# optocouplers2.net
KiCad netlist of a schematic drawn in Altium Designer
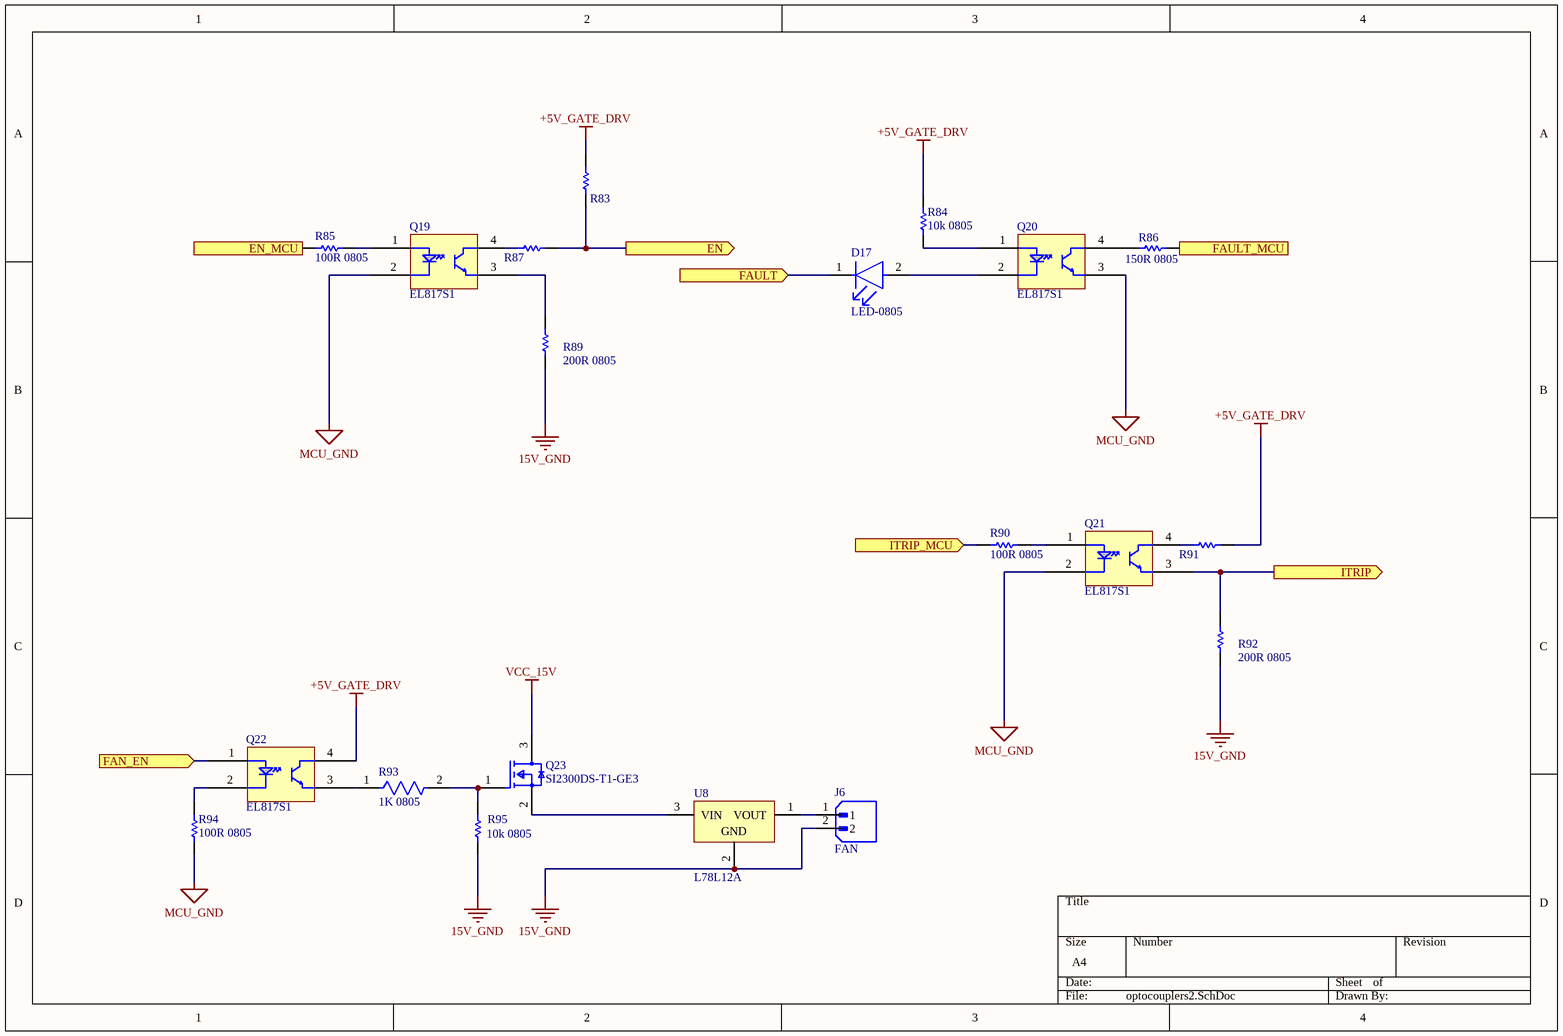
[diagram p0: optocouplers2.SchDoc]

(export (version "E")
  (design (tool "Eeschema 10.0.6"))
  (components
    (comp (ref "D17")
      (value "LED-0805")
      (footprint "LED0805")
      (description "Red LED – 0805 SMD Package – 17-21SURC/S530-A3/TR8")
      (libsource (lib "1kW_BLDC_Controller") (part "LED-0805"))
    )
    (comp (ref "J6")
      (value "FAN")
      (footprint "XH2.5-2p")
      (description "2 Pin JST-XH Male Straight 2515 Connector 2.54mm Pitch")
      (libsource (lib "1kW_BLDC_Controller_1") (part "XH2.5-2p"))
    )
    (comp (ref "Q19")
      (value "EL817S1")
      (footprint "EL817S1")
      (description "EL817S1 (B) (TU) – F Optocoupler SMD-4 Cut Tape")
      (libsource (lib "1kW_BLDC_Controller") (part "EL817S1"))
    )
    (comp (ref "Q20")
      (value "EL817S1")
      (footprint "EL817S1")
      (description "EL817S1 (B) (TU) – F Optocoupler SMD-4 Cut Tape")
      (libsource (lib "1kW_BLDC_Controller") (part "EL817S1"))
    )
    (comp (ref "Q21")
      (value "EL817S1")
      (footprint "EL817S1")
      (description "EL817S1 (B) (TU) – F Optocoupler SMD-4 Cut Tape")
      (libsource (lib "1kW_BLDC_Controller") (part "EL817S1"))
    )
    (comp (ref "Q22")
      (value "EL817S1")
      (footprint "EL817S1")
      (description "EL817S1 (B) (TU) – F Optocoupler SMD-4 Cut Tape")
      (libsource (lib "1kW_BLDC_Controller") (part "EL817S1"))
    )
    (comp (ref "Q23")
      (value "SI2300DS-T1-GE3")
      (footprint "FP-S-03946-MFG")
      (description "SI2300DS 30V 3.6A N-Channel Mosfet – SOT-23 Package")
      (fields
        (field (name "MANUFACTURER") "Vishay")
        (field (name "OCTOPART") "https://octopart.com/si2300ds-t1-ge3-vishay-44451512")
      )
      (libsource (lib "Altium Content Vault") (part "0a9ea7c96deaaede766a5b531c28de0"))
    )
    (comp (ref "R83")
      (value "0R 0603")
      (footprint "R0603")
      (description "0 Ohm 1/10 Watt Resistor 1% Tolerance RC0603FR-070RL – 0603 Package")
      (libsource (lib "1kW_BLDC_Controller") (part "R0000 0603"))
    )
    (comp (ref "R84")
      (value "10k 0805")
      (footprint "R0805")
      (description "10K Ohm 1/8 Watt Resistor 1% Tolerance RC0805FR-0710KL – 0805 Package")
      (libsource (lib "1kW_BLDC_Controller") (part "10k 0805"))
    )
    (comp (ref "R85")
      (value "100R 0805")
      (footprint "R0805")
      (description "100 ohm 1/4W Resistor 0805 Package")
      (libsource (lib "1kW_BLDC_Controller") (part "100R 0805"))
    )
    (comp (ref "R86")
      (value "150R 0805")
      (footprint "R0805")
      (description "510 Ohm 1/8 Watt Resistor 1% Tolerance 0805S8F5100T5E – 0805 Package")
      (libsource (lib "1kW_BLDC_Controller") (part "R0805"))
    )
    (comp (ref "R87")
      (value "0R 0603")
      (footprint "R0603")
      (description "0 Ohm 1/10 Watt Resistor 1% Tolerance RC0603FR-070RL – 0603 Package")
      (libsource (lib "1kW_BLDC_Controller") (part "R0000 0603"))
    )
    (comp (ref "R89")
      (value "200R 0805")
      (footprint "R0805")
      (description "200 Ohm 1/8 Watt Resistor 1% Tolerance 0805W8F2000TE – 0805 Package")
      (libsource (lib "1kW_BLDC_Controller") (part "R0805"))
    )
    (comp (ref "R90")
      (value "100R 0805")
      (footprint "R0805")
      (description "100 ohm 1/4W Resistor 0805 Package")
      (libsource (lib "1kW_BLDC_Controller") (part "100R 0805"))
    )
    (comp (ref "R91")
      (value "0R 0603")
      (footprint "R0603")
      (description "0 Ohm 1/10 Watt Resistor 1% Tolerance RC0603FR-070RL – 0603 Package")
      (libsource (lib "1kW_BLDC_Controller") (part "R0000 0603"))
    )
    (comp (ref "R92")
      (value "200R 0805")
      (footprint "R0805")
      (description "200 Ohm 1/8 Watt Resistor 1% Tolerance 0805W8F2000TE – 0805 Package")
      (libsource (lib "1kW_BLDC_Controller") (part "R0805"))
    )
    (comp (ref "R93")
      (value "1K 0805")
      (footprint "R0805")
      (description "1K Ohm 1/8 Watt Resistor 1% Tolerance 0805S8F1001T5E – 0805 Package")
      (libsource (lib "1kW_BLDC_Controller") (part "1k 0805"))
    )
    (comp (ref "R94")
      (value "100R 0805")
      (footprint "R0805")
      (description "100 ohm 1/4W Resistor 0805 Package")
      (libsource (lib "1kW_BLDC_Controller") (part "100R 0805"))
    )
    (comp (ref "R95")
      (value "10k 0805")
      (footprint "R0805")
      (description "10K Ohm 1/8 Watt Resistor 1% Tolerance RC0805FR-0710KL – 0805 Package")
      (libsource (lib "1kW_BLDC_Controller") (part "10k 0805"))
    )
    (comp (ref "U8")
      (value "L78L12A")
      (footprint "SOT-89_L")
      (description "78L12 – 12V 150mA Positive Voltage Regulator-SOT-89 Package")
      (libsource (lib "Altium Content Vault") (part "PM-REG-7805-SIL3"))
    )
  )
  (nets
    (net (code "1") (name "+5V_GATE_DRV") (class "Default")
      (node (ref "Q22") (pin "4") (pinfunction "C_4") (pintype "passive"))
      (node (ref "R83") (pin "2") (pinfunction "2_2") (pintype "passive"))
      (node (ref "R84") (pin "2") (pinfunction "2_2") (pintype "passive"))
      (node (ref "R91") (pin "2") (pinfunction "2_2") (pintype "passive"))
    )
    (net (code "2") (name "/EN") (class "Default")
      (node (ref "R83") (pin "1") (pinfunction "1_1") (pintype "passive"))
      (node (ref "R87") (pin "2") (pinfunction "2_2") (pintype "passive"))
    )
    (net (code "3") (name "/EN_MCU") (class "Default")
      (node (ref "R85") (pin "1") (pinfunction "1_1") (pintype "passive"))
    )
    (net (code "4") (name "/FAN_EN") (class "Default")
      (node (ref "Q22") (pin "1") (pinfunction "A_1") (pintype "passive"))
    )
    (net (code "5") (name "/FAULT") (class "Default")
      (node (ref "D17") (pin "1") (pinfunction "C_1") (pintype "passive"))
    )
    (net (code "6") (name "/FAULT_MCU") (class "Default")
      (node (ref "R86") (pin "2") (pinfunction "2_2") (pintype "passive"))
    )
    (net (code "7") (name "/ITRIP") (class "Default")
      (node (ref "Q21") (pin "3") (pinfunction "E_3") (pintype "passive"))
      (node (ref "R92") (pin "2") (pinfunction "2_2") (pintype "passive"))
    )
    (net (code "8") (name "/ITRIP_MCU") (class "Default")
      (node (ref "R90") (pin "1") (pinfunction "1_1") (pintype "passive"))
    )
    (net (code "9") (name "15V_GND") (class "Default")
      (node (ref "J6") (pin "2") (pinfunction "2_2") (pintype "passive"))
      (node (ref "R89") (pin "1") (pinfunction "1_1") (pintype "passive"))
      (node (ref "R92") (pin "1") (pinfunction "1_1") (pintype "passive"))
      (node (ref "R95") (pin "1") (pinfunction "1_1") (pintype "passive"))
      (node (ref "U8") (pin "2") (pinfunction "GND_2") (pintype "power_in"))
    )
    (net (code "10") (name "MCU_GND") (class "Default")
      (node (ref "Q19") (pin "2") (pinfunction "K_2") (pintype "passive"))
      (node (ref "Q20") (pin "3") (pinfunction "E_3") (pintype "passive"))
      (node (ref "Q21") (pin "2") (pinfunction "K_2") (pintype "passive"))
      (node (ref "R94") (pin "1") (pinfunction "1_1") (pintype "passive"))
    )
    (net (code "11") (name "Net-(D17-A)") (class "Default")
      (node (ref "D17") (pin "2") (pinfunction "A_2") (pintype "passive"))
      (node (ref "Q20") (pin "2") (pinfunction "K_2") (pintype "passive"))
    )
    (net (code "12") (name "Net-(Q19-A)") (class "Default")
      (node (ref "Q19") (pin "1") (pinfunction "A_1") (pintype "passive"))
      (node (ref "R85") (pin "2") (pinfunction "2_2") (pintype "passive"))
    )
    (net (code "13") (name "Net-(Q19-C)") (class "Default")
      (node (ref "Q19") (pin "4") (pinfunction "C_4") (pintype "passive"))
      (node (ref "R87") (pin "1") (pinfunction "1_1") (pintype "passive"))
    )
    (net (code "14") (name "Net-(Q19-E)") (class "Default")
      (node (ref "Q19") (pin "3") (pinfunction "E_3") (pintype "passive"))
      (node (ref "R89") (pin "2") (pinfunction "2_2") (pintype "passive"))
    )
    (net (code "15") (name "Net-(Q20-A)") (class "Default")
      (node (ref "Q20") (pin "1") (pinfunction "A_1") (pintype "passive"))
      (node (ref "R84") (pin "1") (pinfunction "1_1") (pintype "passive"))
    )
    (net (code "16") (name "Net-(Q20-C)") (class "Default")
      (node (ref "Q20") (pin "4") (pinfunction "C_4") (pintype "passive"))
      (node (ref "R86") (pin "1") (pinfunction "1_1") (pintype "passive"))
    )
    (net (code "17") (name "Net-(Q21-A)") (class "Default")
      (node (ref "Q21") (pin "1") (pinfunction "A_1") (pintype "passive"))
      (node (ref "R90") (pin "2") (pinfunction "2_2") (pintype "passive"))
    )
    (net (code "18") (name "Net-(Q21-C)") (class "Default")
      (node (ref "Q21") (pin "4") (pinfunction "C_4") (pintype "passive"))
      (node (ref "R91") (pin "1") (pinfunction "1_1") (pintype "passive"))
    )
    (net (code "19") (name "Net-(Q22-E)") (class "Default")
      (node (ref "Q22") (pin "3") (pinfunction "E_3") (pintype "passive"))
      (node (ref "R93") (pin "1") (pinfunction "1_1") (pintype "passive"))
    )
    (net (code "20") (name "Net-(Q22-K)") (class "Default")
      (node (ref "Q22") (pin "2") (pinfunction "K_2") (pintype "passive"))
      (node (ref "R94") (pin "2") (pinfunction "2_2") (pintype "passive"))
    )
    (net (code "21") (name "Net-(Q23-G)") (class "Default")
      (node (ref "Q23") (pin "1") (pinfunction "G_1") (pintype "passive"))
      (node (ref "R93") (pin "2") (pinfunction "2_2") (pintype "passive"))
      (node (ref "R95") (pin "2") (pinfunction "2_2") (pintype "passive"))
    )
    (net (code "22") (name "Net-(Q23-S)") (class "Default")
      (node (ref "Q23") (pin "2") (pinfunction "S_2") (pintype "passive"))
      (node (ref "U8") (pin "3") (pinfunction "VIN_3") (pintype "power_in"))
    )
    (net (code "23") (name "Net-(U8-VOUT)") (class "Default")
      (node (ref "J6") (pin "1") (pinfunction "1_1") (pintype "passive"))
      (node (ref "U8") (pin "1") (pinfunction "VOUT_1") (pintype "power_in"))
    )
    (net (code "24") (name "VCC_15V") (class "Default")
      (node (ref "Q23") (pin "3") (pinfunction "D_3") (pintype "passive"))
    )
  )
)
